# 16bit-v0_5.net
KiCad netlist of a schematic drawn in EAGLE
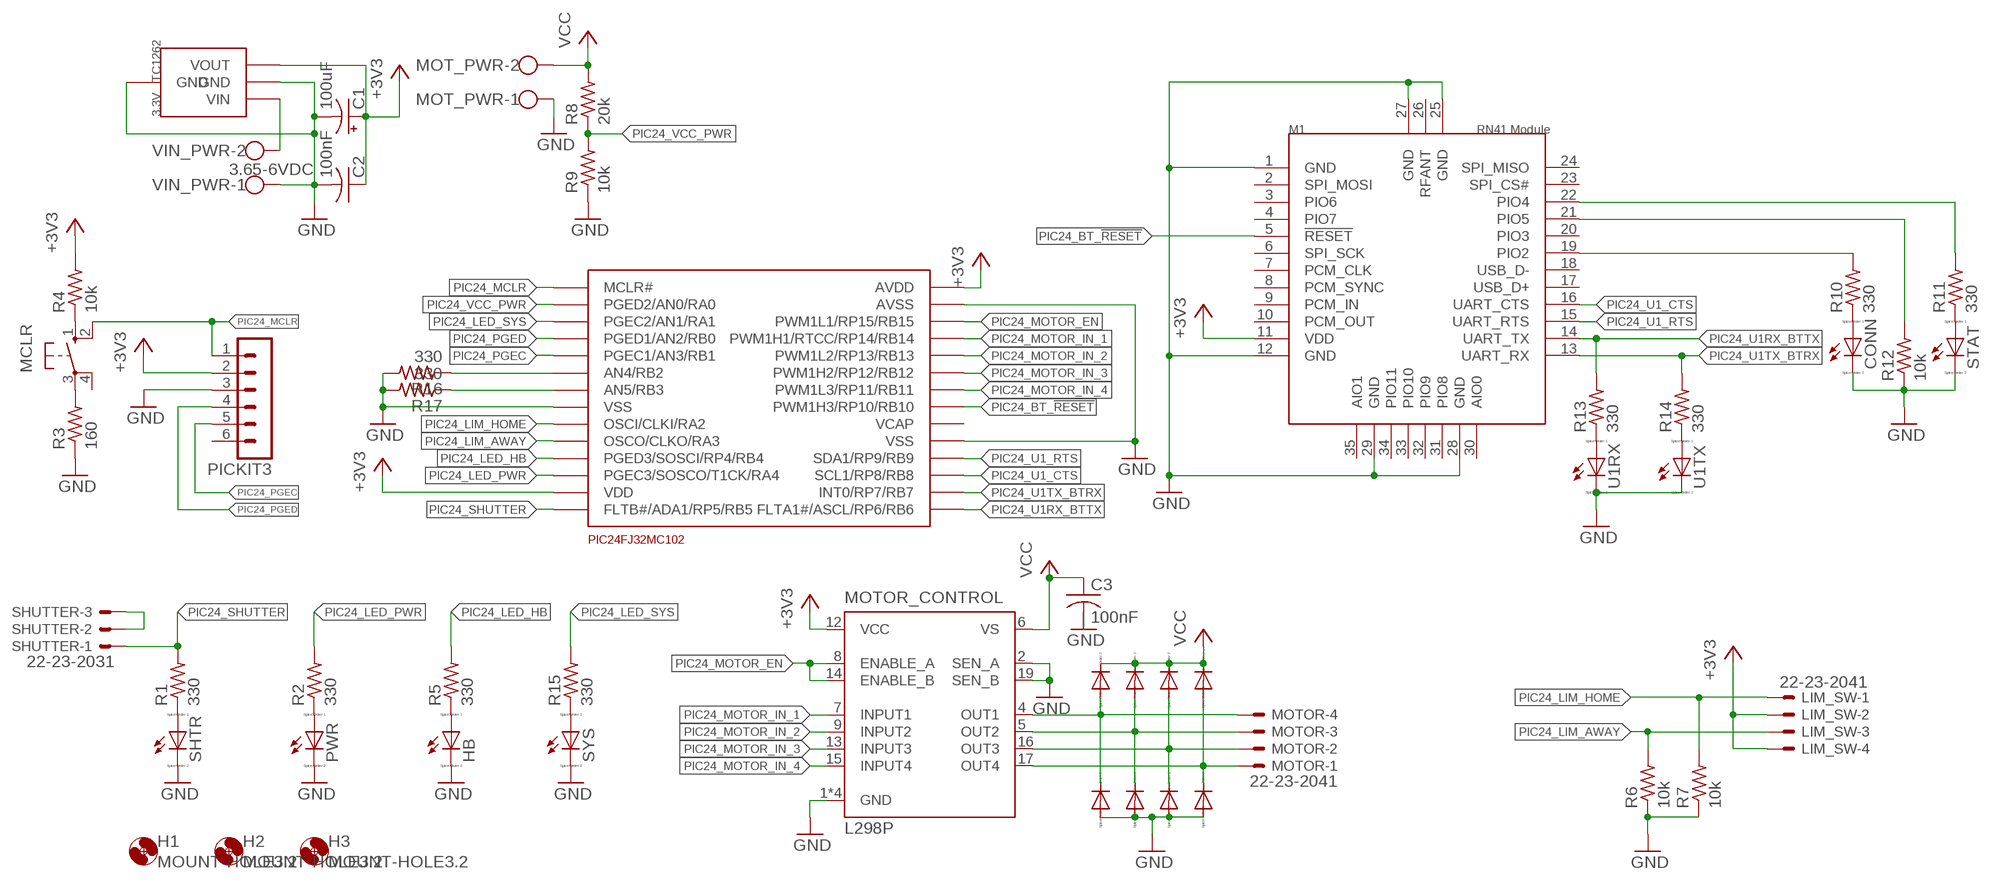
[diagram p0: schematic, sheet 1]

(export (version "E")
  (design (tool "Eeschema 10.0.6"))
  (components
    (comp (ref "C1")
      (value "100uF")
      (footprint "eagle-import:E2,5-7")
      (libsource (lib "eagle-import") (part "CPOL-USE2.5-7"))
    )
    (comp (ref "C2")
      (value "100nF")
      (footprint "eagle-import:C0402")
      (libsource (lib "eagle-import") (part "C-USC0402"))
    )
    (comp (ref "C3")
      (value "100nF")
      (footprint "eagle-import:C0402")
      (libsource (lib "eagle-import") (part "C-USC0402"))
    )
    (comp (ref "CONN")
      (value "LED_ESML0603")
      (footprint "eagle-import:LED_SML0603")
      (libsource (lib "eagle-import") (part "LED_ESML0603"))
    )
    (comp (ref "D1")
      (value "DIODE-SMB")
      (footprint "eagle-import:SMB")
      (libsource (lib "eagle-import") (part "DIODE-SMB"))
    )
    (comp (ref "D2")
      (value "DIODE-SMB")
      (footprint "eagle-import:SMB")
      (libsource (lib "eagle-import") (part "DIODE-SMB"))
    )
    (comp (ref "D3")
      (value "DIODE-SMB")
      (footprint "eagle-import:SMB")
      (libsource (lib "eagle-import") (part "DIODE-SMB"))
    )
    (comp (ref "D4")
      (value "DIODE-SMB")
      (footprint "eagle-import:SMB")
      (libsource (lib "eagle-import") (part "DIODE-SMB"))
    )
    (comp (ref "D5")
      (value "DIODE-SMB")
      (footprint "eagle-import:SMB")
      (libsource (lib "eagle-import") (part "DIODE-SMB"))
    )
    (comp (ref "D6")
      (value "DIODE-SMB")
      (footprint "eagle-import:SMB")
      (libsource (lib "eagle-import") (part "DIODE-SMB"))
    )
    (comp (ref "D7")
      (value "DIODE-SMB")
      (footprint "eagle-import:SMB")
      (libsource (lib "eagle-import") (part "DIODE-SMB"))
    )
    (comp (ref "D8")
      (value "DIODE-SMB")
      (footprint "eagle-import:SMB")
      (libsource (lib "eagle-import") (part "DIODE-SMB"))
    )
    (comp (ref "H1")
      (value "MOUNT-HOLE3.2")
      (footprint "eagle-import:3,2")
      (libsource (lib "eagle-import") (part "MOUNT-HOLE3.2"))
    )
    (comp (ref "H2")
      (value "MOUNT-HOLE3.2")
      (footprint "eagle-import:3,2")
      (libsource (lib "eagle-import") (part "MOUNT-HOLE3.2"))
    )
    (comp (ref "H3")
      (value "MOUNT-HOLE3.2")
      (footprint "eagle-import:3,2")
      (libsource (lib "eagle-import") (part "MOUNT-HOLE3.2"))
    )
    (comp (ref "HB")
      (value "LED_ESML0603")
      (footprint "eagle-import:LED_SML0603")
      (libsource (lib "eagle-import") (part "LED_ESML0603"))
    )
    (comp (ref "LIM_SW")
      (value "22-23-2041")
      (footprint "eagle-import:22-23-2041")
      (fields (field (name "MF") "MOLEX"))
      (libsource (lib "eagle-import") (part "22-23-2041"))
    )
    (comp (ref "MCLR")
      (value "10-XX")
      (footprint "eagle-import:B3F-10XX")
      (fields (field (name "MPN") "B3F-1000"))
      (libsource (lib "eagle-import") (part "10-XX"))
    )
    (comp (ref "MOTOR")
      (value "22-23-2041")
      (footprint "eagle-import:22-23-2041")
      (fields (field (name "MF") "MOLEX"))
      (libsource (lib "eagle-import") (part "22-23-2041"))
    )
    (comp (ref "MOTOR_CONTROL")
      (value "L298P")
      (footprint "eagle-import:POWERSO-20")
      (libsource (lib "eagle-import") (part "L298P"))
    )
    (comp (ref "MOT_PWR")
      (value "W237-102")
      (footprint "eagle-import:W237-102")
      (fields (field (name "MPN") "237-102"))
      (libsource (lib "eagle-import") (part "W237-102"))
    )
    (comp (ref "PICKIT3")
      (value "MA06-1")
      (footprint "eagle-import:MA06-1")
      (libsource (lib "eagle-import") (part "MA06-1"))
    )
    (comp (ref "PWR")
      (value "LED_ESML0603")
      (footprint "eagle-import:LED_SML0603")
      (libsource (lib "eagle-import") (part "LED_ESML0603"))
    )
    (comp (ref "R1")
      (value "330")
      (footprint "eagle-import:R0603")
      (libsource (lib "eagle-import") (part "R-US_R0603"))
    )
    (comp (ref "R2")
      (value "330")
      (footprint "eagle-import:R0603")
      (libsource (lib "eagle-import") (part "R-US_R0603"))
    )
    (comp (ref "R3")
      (value "160")
      (footprint "eagle-import:R0603")
      (libsource (lib "eagle-import") (part "R-US_R0603"))
    )
    (comp (ref "R4")
      (value "10k")
      (footprint "eagle-import:R0603")
      (libsource (lib "eagle-import") (part "R-US_R0603"))
    )
    (comp (ref "R5")
      (value "330")
      (footprint "eagle-import:R0603")
      (libsource (lib "eagle-import") (part "R-US_R0603"))
    )
    (comp (ref "R6")
      (value "10k")
      (footprint "eagle-import:R0603")
      (libsource (lib "eagle-import") (part "R-US_R0603"))
    )
    (comp (ref "R7")
      (value "10k")
      (footprint "eagle-import:R0603")
      (libsource (lib "eagle-import") (part "R-US_R0603"))
    )
    (comp (ref "R8")
      (value "20k")
      (footprint "eagle-import:R0603")
      (libsource (lib "eagle-import") (part "R-US_R0603"))
    )
    (comp (ref "R9")
      (value "10k")
      (footprint "eagle-import:R0603")
      (libsource (lib "eagle-import") (part "R-US_R0603"))
    )
    (comp (ref "R10")
      (value "330")
      (footprint "eagle-import:R0603")
      (libsource (lib "eagle-import") (part "R-US_R0603"))
    )
    (comp (ref "R11")
      (value "330")
      (footprint "eagle-import:R0603")
      (libsource (lib "eagle-import") (part "R-US_R0603"))
    )
    (comp (ref "R12")
      (value "10k")
      (footprint "eagle-import:R0603")
      (libsource (lib "eagle-import") (part "R-US_R0603"))
    )
    (comp (ref "R13")
      (value "330")
      (footprint "eagle-import:R0603")
      (libsource (lib "eagle-import") (part "R-US_R0603"))
    )
    (comp (ref "R14")
      (value "330")
      (footprint "eagle-import:R0603")
      (libsource (lib "eagle-import") (part "R-US_R0603"))
    )
    (comp (ref "R15")
      (value "330")
      (footprint "eagle-import:R0603")
      (libsource (lib "eagle-import") (part "R-US_R0603"))
    )
    (comp (ref "R16")
      (value "330")
      (footprint "eagle-import:R0603")
      (libsource (lib "eagle-import") (part "R-US_R0603"))
    )
    (comp (ref "R17")
      (value "330")
      (footprint "eagle-import:R0603")
      (libsource (lib "eagle-import") (part "R-US_R0603"))
    )
    (comp (ref "SHTR")
      (value "LED_ESML0603")
      (footprint "eagle-import:LED_SML0603")
      (libsource (lib "eagle-import") (part "LED_ESML0603"))
    )
    (comp (ref "SHUTTER")
      (value "22-23-2031")
      (footprint "eagle-import:22-23-2031")
      (fields (field (name "MF") "MOLEX"))
      (libsource (lib "eagle-import") (part "22-23-2031"))
    )
    (comp (ref "STAT")
      (value "LED_ESML0603")
      (footprint "eagle-import:LED_SML0603")
      (libsource (lib "eagle-import") (part "LED_ESML0603"))
    )
    (comp (ref "SYS")
      (value "LED_ESML0603")
      (footprint "eagle-import:LED_SML0603")
      (libsource (lib "eagle-import") (part "LED_ESML0603"))
    )
    (comp (ref "U$1")
      (value "PIC24FJ32MC102")
      (footprint "eagle-import:PIC2428-SOIC")
      (libsource (lib "eagle-import") (part "PIC24FJ32MC102"))
    )
    (comp (ref "U$2")
      (value "RN41N")
      (footprint "eagle-import:RN41N")
      (libsource (lib "eagle-import") (part "RN41N"))
    )
    (comp (ref "U$3")
      (value "TC1262-3.3VDBTR")
      (footprint "eagle-import:TO-261-4")
      (libsource (lib "eagle-import") (part "TC1262-3.3VDBTR"))
    )
    (comp (ref "U1RX")
      (value "LED_ESML0603")
      (footprint "eagle-import:LED_SML0603")
      (libsource (lib "eagle-import") (part "LED_ESML0603"))
    )
    (comp (ref "U1TX")
      (value "LED_ESML0603")
      (footprint "eagle-import:LED_SML0603")
      (libsource (lib "eagle-import") (part "LED_ESML0603"))
    )
    (comp (ref "VIN_PWR")
      (value "3.65-6VDC")
      (footprint "eagle-import:W237-102")
      (fields (field (name "MPN") "237-102"))
      (libsource (lib "eagle-import") (part "W237-102"))
    )
  )
  (nets
    (net (code "1") (name "+3V3") (class "Default")
      (node (ref "C1") (pin "+") (pinfunction "+_+") (pintype "passive"))
      (node (ref "C2") (pin "1") (pinfunction "1_1") (pintype "passive"))
      (node (ref "LIM_SW") (pin "2") (pinfunction "S_2") (pintype "passive"))
      (node (ref "LIM_SW") (pin "4") (pinfunction "S_4") (pintype "passive"))
      (node (ref "MOTOR_CONTROL") (pin "12") (pinfunction "VCC_12") (pintype "power_in"))
      (node (ref "PICKIT3") (pin "2") (pinfunction "2_2") (pintype "passive"))
      (node (ref "R4") (pin "2") (pinfunction "2_2") (pintype "passive"))
      (node (ref "U$1") (pin "AVDD") (pinfunction "AVDD_AVDD") (pintype "bidirectional"))
      (node (ref "U$1") (pin "VDD") (pinfunction "VDD_VDD") (pintype "bidirectional"))
      (node (ref "U$2") (pin "11") (pinfunction "VDD_11") (pintype "bidirectional"))
      (node (ref "U$3") (pin "P$3") (pinfunction "VOUT_P$3") (pintype "bidirectional"))
    )
    (net (code "2") (name "/PIC24_BT_~{RESET}") (class "Default")
      (node (ref "U$1") (pin "RB10") (pinfunction "PWM1H3/RP10/RB10_RB10") (pintype "bidirectional"))
      (node (ref "U$2") (pin "5") (pinfunction "~{RESET}_5") (pintype "bidirectional"))
    )
    (net (code "3") (name "GND") (class "Default")
      (node (ref "C1") (pin "-") (pinfunction "-_-") (pintype "passive"))
      (node (ref "C2") (pin "2") (pinfunction "2_2") (pintype "passive"))
      (node (ref "C3") (pin "2") (pinfunction "2_2") (pintype "passive"))
      (node (ref "CONN") (pin "C") (pinfunction "C_C") (pintype "passive"))
      (node (ref "D5") (pin "A") (pinfunction "A_A") (pintype "passive"))
      (node (ref "D6") (pin "A") (pinfunction "A_A") (pintype "passive"))
      (node (ref "D7") (pin "A") (pinfunction "A_A") (pintype "passive"))
      (node (ref "D8") (pin "A") (pinfunction "A_A") (pintype "passive"))
      (node (ref "HB") (pin "C") (pinfunction "C_C") (pintype "passive"))
      (node (ref "MOTOR_CONTROL") (pin "1") (pinfunction "GND_1") (pintype "power_in"))
      (node (ref "MOTOR_CONTROL") (pin "10") (pinfunction "GND_10") (pintype "power_in"))
      (node (ref "MOTOR_CONTROL") (pin "11") (pinfunction "GND_11") (pintype "power_in"))
      (node (ref "MOTOR_CONTROL") (pin "19") (pinfunction "SEN_B_19") (pintype "input"))
      (node (ref "MOTOR_CONTROL") (pin "2") (pinfunction "SEN_A_2") (pintype "input"))
      (node (ref "MOTOR_CONTROL") (pin "20") (pinfunction "GND_20") (pintype "power_in"))
      (node (ref "MOT_PWR") (pin "1") (pinfunction "KL_1") (pintype "passive"))
      (node (ref "PICKIT3") (pin "3") (pinfunction "3_3") (pintype "passive"))
      (node (ref "PWR") (pin "C") (pinfunction "C_C") (pintype "passive"))
      (node (ref "R12") (pin "1") (pinfunction "1_1") (pintype "passive"))
      (node (ref "R16") (pin "2") (pinfunction "2_2") (pintype "passive"))
      (node (ref "R17") (pin "2") (pinfunction "2_2") (pintype "passive"))
      (node (ref "R3") (pin "1") (pinfunction "1_1") (pintype "passive"))
      (node (ref "R6") (pin "1") (pinfunction "1_1") (pintype "passive"))
      (node (ref "R7") (pin "1") (pinfunction "1_1") (pintype "passive"))
      (node (ref "R9") (pin "1") (pinfunction "1_1") (pintype "passive"))
      (node (ref "SHTR") (pin "C") (pinfunction "C_C") (pintype "passive"))
      (node (ref "STAT") (pin "C") (pinfunction "C_C") (pintype "passive"))
      (node (ref "SYS") (pin "C") (pinfunction "C_C") (pintype "passive"))
      (node (ref "U$1") (pin "AVSS") (pinfunction "AVSS_AVSS") (pintype "bidirectional"))
      (node (ref "U$1") (pin "VSS@19") (pinfunction "VSS_VSS@19") (pintype "bidirectional"))
      (node (ref "U$1") (pin "VSS@8") (pinfunction "VSS_VSS@8") (pintype "bidirectional"))
      (node (ref "U$2") (pin "1") (pinfunction "GND_1") (pintype "bidirectional"))
      (node (ref "U$2") (pin "12") (pinfunction "GND_12") (pintype "bidirectional"))
      (node (ref "U$2") (pin "25") (pinfunction "GND_25") (pintype "bidirectional"))
      (node (ref "U$2") (pin "27") (pinfunction "GND_27") (pintype "bidirectional"))
      (node (ref "U$2") (pin "28") (pinfunction "GND_28") (pintype "bidirectional"))
      (node (ref "U$2") (pin "29") (pinfunction "GND_29") (pintype "bidirectional"))
      (node (ref "U$3") (pin "P$2") (pinfunction "GND_P$2") (pintype "bidirectional"))
      (node (ref "U$3") (pin "P$4") (pinfunction "GND_P$4") (pintype "bidirectional"))
      (node (ref "U1RX") (pin "C") (pinfunction "C_C") (pintype "passive"))
      (node (ref "U1TX") (pin "C") (pinfunction "C_C") (pintype "passive"))
      (node (ref "VIN_PWR") (pin "1") (pinfunction "KL_1") (pintype "passive"))
    )
    (net (code "4") (name "Net-(CONN-PadA)") (class "Default")
      (node (ref "CONN") (pin "A") (pinfunction "A_A") (pintype "passive"))
      (node (ref "R10") (pin "1") (pinfunction "1_1") (pintype "passive"))
    )
    (net (code "5") (name "Net-(HB-PadA)") (class "Default")
      (node (ref "HB") (pin "A") (pinfunction "A_A") (pintype "passive"))
      (node (ref "R5") (pin "1") (pinfunction "1_1") (pintype "passive"))
    )
    (net (code "6") (name "Net-(MCLR-P)") (class "Default")
      (node (ref "MCLR") (pin "3") (pinfunction "P_3") (pintype "passive"))
      (node (ref "R3") (pin "2") (pinfunction "2_2") (pintype "passive"))
    )
    (net (code "7") (name "Net-(MCLR-S)") (class "Default")
      (node (ref "MCLR") (pin "1") (pinfunction "S_1") (pintype "passive"))
      (node (ref "R4") (pin "1") (pinfunction "1_1") (pintype "passive"))
    )
    (net (code "8") (name "Net-(MOTORA-S)") (class "Default")
      (node (ref "D4") (pin "A") (pinfunction "A_A") (pintype "passive"))
      (node (ref "D8") (pin "C") (pinfunction "C_C") (pintype "passive"))
      (node (ref "MOTOR") (pin "1") (pinfunction "S_1") (pintype "passive"))
      (node (ref "MOTOR_CONTROL") (pin "17") (pinfunction "OUT4_17") (pintype "output"))
    )
    (net (code "9") (name "Net-(MOTORB-S)") (class "Default")
      (node (ref "D3") (pin "A") (pinfunction "A_A") (pintype "passive"))
      (node (ref "D7") (pin "C") (pinfunction "C_C") (pintype "passive"))
      (node (ref "MOTOR") (pin "2") (pinfunction "S_2") (pintype "passive"))
      (node (ref "MOTOR_CONTROL") (pin "16") (pinfunction "OUT3_16") (pintype "output"))
    )
    (net (code "10") (name "Net-(MOTORC-S)") (class "Default")
      (node (ref "D2") (pin "A") (pinfunction "A_A") (pintype "passive"))
      (node (ref "D6") (pin "C") (pinfunction "C_C") (pintype "passive"))
      (node (ref "MOTOR") (pin "3") (pinfunction "S_3") (pintype "passive"))
      (node (ref "MOTOR_CONTROL") (pin "5") (pinfunction "OUT2_5") (pintype "output"))
    )
    (net (code "11") (name "Net-(MOTORD-S)") (class "Default")
      (node (ref "D1") (pin "A") (pinfunction "A_A") (pintype "passive"))
      (node (ref "D5") (pin "C") (pinfunction "C_C") (pintype "passive"))
      (node (ref "MOTOR") (pin "4") (pinfunction "S_4") (pintype "passive"))
      (node (ref "MOTOR_CONTROL") (pin "4") (pinfunction "OUT1_4") (pintype "output"))
    )
    (net (code "12") (name "Net-(PWR-PadA)") (class "Default")
      (node (ref "PWR") (pin "A") (pinfunction "A_A") (pintype "passive"))
      (node (ref "R2") (pin "1") (pinfunction "1_1") (pintype "passive"))
    )
    (net (code "13") (name "Net-(R1-Pad1)") (class "Default")
      (node (ref "R1") (pin "1") (pinfunction "1_1") (pintype "passive"))
      (node (ref "SHTR") (pin "A") (pinfunction "A_A") (pintype "passive"))
    )
    (net (code "14") (name "Net-(R11-Pad1)") (class "Default")
      (node (ref "R11") (pin "1") (pinfunction "1_1") (pintype "passive"))
      (node (ref "STAT") (pin "A") (pinfunction "A_A") (pintype "passive"))
    )
    (net (code "15") (name "Net-(R13-Pad1)") (class "Default")
      (node (ref "R13") (pin "1") (pinfunction "1_1") (pintype "passive"))
      (node (ref "U1RX") (pin "A") (pinfunction "A_A") (pintype "passive"))
    )
    (net (code "16") (name "Net-(R14-Pad1)") (class "Default")
      (node (ref "R14") (pin "1") (pinfunction "1_1") (pintype "passive"))
      (node (ref "U1TX") (pin "A") (pinfunction "A_A") (pintype "passive"))
    )
    (net (code "17") (name "Net-(R15-Pad1)") (class "Default")
      (node (ref "R15") (pin "1") (pinfunction "1_1") (pintype "passive"))
      (node (ref "SYS") (pin "A") (pinfunction "A_A") (pintype "passive"))
    )
    (net (code "18") (name "Net-(SHUTTERB-S)") (class "Default")
      (node (ref "SHUTTER") (pin "2") (pinfunction "S_2") (pintype "passive"))
      (node (ref "SHUTTER") (pin "3") (pinfunction "S_3") (pintype "passive"))
    )
    (net (code "19") (name "Net-(U$1-AN4{slash}RB2)") (class "Default")
      (node (ref "R16") (pin "1") (pinfunction "1_1") (pintype "passive"))
      (node (ref "U$1") (pin "RB2") (pinfunction "AN4/RB2_RB2") (pintype "bidirectional"))
    )
    (net (code "20") (name "Net-(U$1-AN5{slash}RB3)") (class "Default")
      (node (ref "R17") (pin "1") (pinfunction "1_1") (pintype "passive"))
      (node (ref "U$1") (pin "RB3") (pinfunction "AN5/RB3_RB3") (pintype "bidirectional"))
    )
    (net (code "21") (name "Net-(U$2-PIO2)") (class "Default")
      (node (ref "R10") (pin "2") (pinfunction "2_2") (pintype "passive"))
      (node (ref "U$2") (pin "19") (pinfunction "PIO2_19") (pintype "bidirectional"))
    )
    (net (code "22") (name "Net-(U$2-PIO4)") (class "Default")
      (node (ref "R11") (pin "2") (pinfunction "2_2") (pintype "passive"))
      (node (ref "U$2") (pin "22") (pinfunction "PIO4_22") (pintype "bidirectional"))
    )
    (net (code "23") (name "Net-(U$2-PIO5)") (class "Default")
      (node (ref "R12") (pin "2") (pinfunction "2_2") (pintype "passive"))
      (node (ref "U$2") (pin "21") (pinfunction "PIO5_21") (pintype "bidirectional"))
    )
    (net (code "24") (name "Net-(U$3-VIN)") (class "Default")
      (node (ref "U$3") (pin "P$1") (pinfunction "VIN_P$1") (pintype "bidirectional"))
      (node (ref "VIN_PWR") (pin "2") (pinfunction "KL_2") (pintype "passive"))
    )
    (net (code "25") (name "PIC24_LED_HB") (class "Default")
      (node (ref "R5") (pin "2") (pinfunction "2_2") (pintype "passive"))
      (node (ref "U$1") (pin "RB4") (pinfunction "PGED3/SOSCI/RP4/RB4_RB4") (pintype "bidirectional"))
    )
    (net (code "26") (name "PIC24_LED_PWR") (class "Default")
      (node (ref "R2") (pin "2") (pinfunction "2_2") (pintype "passive"))
      (node (ref "U$1") (pin "RA4") (pinfunction "PGEC3/SOSCO/T1CK/RA4_RA4") (pintype "bidirectional"))
    )
    (net (code "27") (name "PIC24_LED_SYS") (class "Default")
      (node (ref "R15") (pin "2") (pinfunction "2_2") (pintype "passive"))
      (node (ref "U$1") (pin "RA1") (pinfunction "PGEC2/AN1/RA1_RA1") (pintype "bidirectional"))
    )
    (net (code "28") (name "PIC24_LIM_AWAY") (class "Default")
      (node (ref "LIM_SW") (pin "3") (pinfunction "S_3") (pintype "passive"))
      (node (ref "R6") (pin "2") (pinfunction "2_2") (pintype "passive"))
      (node (ref "U$1") (pin "RA3") (pinfunction "OSCO/CLKO/RA3_RA3") (pintype "bidirectional"))
    )
    (net (code "29") (name "PIC24_LIM_HOME") (class "Default")
      (node (ref "LIM_SW") (pin "1") (pinfunction "S_1") (pintype "passive"))
      (node (ref "R7") (pin "2") (pinfunction "2_2") (pintype "passive"))
      (node (ref "U$1") (pin "RA2") (pinfunction "OSCI/CLKI/RA2_RA2") (pintype "bidirectional"))
    )
    (net (code "30") (name "PIC24_MCLR") (class "Default")
      (node (ref "MCLR") (pin "2") (pinfunction "S1_2") (pintype "passive"))
      (node (ref "PICKIT3") (pin "1") (pinfunction "1_1") (pintype "passive"))
      (node (ref "U$1") (pin "MCLR#") (pinfunction "MCLR#_MCLR#") (pintype "bidirectional"))
    )
    (net (code "31") (name "PIC24_MOTOR_EN") (class "Default")
      (node (ref "MOTOR_CONTROL") (pin "14") (pinfunction "ENABLE_B_14") (pintype "input"))
      (node (ref "MOTOR_CONTROL") (pin "8") (pinfunction "ENABLE_A_8") (pintype "input"))
      (node (ref "U$1") (pin "RB15") (pinfunction "PWM1L1/RP15/RB15_RB15") (pintype "bidirectional"))
    )
    (net (code "32") (name "PIC24_MOTOR_IN_1") (class "Default")
      (node (ref "MOTOR_CONTROL") (pin "7") (pinfunction "INPUT1_7") (pintype "input"))
      (node (ref "U$1") (pin "RB14") (pinfunction "PWM1H1/RTCC/RP14/RB14_RB14") (pintype "bidirectional"))
    )
    (net (code "33") (name "PIC24_MOTOR_IN_2") (class "Default")
      (node (ref "MOTOR_CONTROL") (pin "9") (pinfunction "INPUT2_9") (pintype "input"))
      (node (ref "U$1") (pin "RB13") (pinfunction "PWM1L2/RP13/RB13_RB13") (pintype "bidirectional"))
    )
    (net (code "34") (name "PIC24_MOTOR_IN_3") (class "Default")
      (node (ref "MOTOR_CONTROL") (pin "13") (pinfunction "INPUT3_13") (pintype "input"))
      (node (ref "U$1") (pin "RB12") (pinfunction "PWM1H2/RP12/RB12_RB12") (pintype "bidirectional"))
    )
    (net (code "35") (name "PIC24_MOTOR_IN_4") (class "Default")
      (node (ref "MOTOR_CONTROL") (pin "15") (pinfunction "INPUT4_15") (pintype "input"))
      (node (ref "U$1") (pin "RB11") (pinfunction "PWM1L3/RP11/RB11_RB11") (pintype "bidirectional"))
    )
    (net (code "36") (name "PIC24_PGEC") (class "Default")
      (node (ref "PICKIT3") (pin "5") (pinfunction "5_5") (pintype "passive"))
      (node (ref "U$1") (pin "PGEC1") (pinfunction "PGEC1/AN3/RB1_PGEC1") (pintype "bidirectional"))
    )
    (net (code "37") (name "PIC24_PGED") (class "Default")
      (node (ref "PICKIT3") (pin "4") (pinfunction "4_4") (pintype "passive"))
      (node (ref "U$1") (pin "PGED1") (pinfunction "PGED1/AN2/RB0_PGED1") (pintype "bidirectional"))
    )
    (net (code "38") (name "PIC24_SHUTTER") (class "Default")
      (node (ref "R1") (pin "2") (pinfunction "2_2") (pintype "passive"))
      (node (ref "SHUTTER") (pin "1") (pinfunction "S_1") (pintype "passive"))
      (node (ref "U$1") (pin "RB5") (pinfunction "FLTB#/ADA1/RP5/RB5_RB5") (pintype "bidirectional"))
    )
    (net (code "39") (name "PIC24_U1RX_BTTX") (class "Default")
      (node (ref "R13") (pin "2") (pinfunction "2_2") (pintype "passive"))
      (node (ref "U$1") (pin "RB6") (pinfunction "FLTA1#/ASCL/RP6/RB6_RB6") (pintype "bidirectional"))
      (node (ref "U$2") (pin "14") (pinfunction "UART_TX_14") (pintype "bidirectional"))
    )
    (net (code "40") (name "PIC24_U1TX_BTRX") (class "Default")
      (node (ref "R14") (pin "2") (pinfunction "2_2") (pintype "passive"))
      (node (ref "U$1") (pin "RB7") (pinfunction "INT0/RP7/RB7_RB7") (pintype "bidirectional"))
      (node (ref "U$2") (pin "13") (pinfunction "UART_RX_13") (pintype "bidirectional"))
    )
    (net (code "41") (name "PIC24_U1_CTS") (class "Default")
      (node (ref "U$1") (pin "RB8") (pinfunction "SCL1/RP8/RB8_RB8") (pintype "bidirectional"))
      (node (ref "U$2") (pin "16") (pinfunction "UART_CTS_16") (pintype "bidirectional"))
    )
    (net (code "42") (name "PIC24_U1_RTS") (class "Default")
      (node (ref "U$1") (pin "RB9") (pinfunction "SDA1/RP9/RB9_RB9") (pintype "bidirectional"))
      (node (ref "U$2") (pin "15") (pinfunction "UART_RTS_15") (pintype "bidirectional"))
    )
    (net (code "43") (name "PIC24_VCC_PWR") (class "Default")
      (node (ref "R8") (pin "1") (pinfunction "1_1") (pintype "passive"))
      (node (ref "R9") (pin "2") (pinfunction "2_2") (pintype "passive"))
      (node (ref "U$1") (pin "RA0") (pinfunction "PGED2/AN0/RA0_RA0") (pintype "bidirectional"))
    )
    (net (code "44") (name "VCC") (class "Default")
      (node (ref "C3") (pin "1") (pinfunction "1_1") (pintype "passive"))
      (node (ref "D1") (pin "C") (pinfunction "C_C") (pintype "passive"))
      (node (ref "D2") (pin "C") (pinfunction "C_C") (pintype "passive"))
      (node (ref "D3") (pin "C") (pinfunction "C_C") (pintype "passive"))
      (node (ref "D4") (pin "C") (pinfunction "C_C") (pintype "passive"))
      (node (ref "MOTOR_CONTROL") (pin "6") (pinfunction "VS_6") (pintype "power_in"))
      (node (ref "MOT_PWR") (pin "2") (pinfunction "KL_2") (pintype "passive"))
      (node (ref "R8") (pin "2") (pinfunction "2_2") (pintype "passive"))
    )
    (net (code "45") (name "unconnected-(MCLR-P1-Pad4)") (class "Default")
      (node (ref "MCLR") (pin "4") (pinfunction "P1_4") (pintype "passive"))
    )
    (net (code "46") (name "unconnected-(PICKIT3-Pad6)") (class "Default")
      (node (ref "PICKIT3") (pin "6") (pinfunction "6_6") (pintype "passive"))
    )
    (net (code "47") (name "unconnected-(U$1-PadVCAP)") (class "Default")
      (node (ref "U$1") (pin "VCAP") (pinfunction "VCAP_VCAP") (pintype "bidirectional"))
    )
    (net (code "48") (name "unconnected-(U$2-AIO0-Pad30)") (class "Default")
      (node (ref "U$2") (pin "30") (pinfunction "AIO0_30") (pintype "bidirectional"))
    )
    (net (code "49") (name "unconnected-(U$2-AIO1-Pad35)") (class "Default")
      (node (ref "U$2") (pin "35") (pinfunction "AIO1_35") (pintype "bidirectional"))
    )
    (net (code "50") (name "unconnected-(U$2-PCM_CLK-Pad7)") (class "Default")
      (node (ref "U$2") (pin "7") (pinfunction "PCM_CLK_7") (pintype "bidirectional"))
    )
    (net (code "51") (name "unconnected-(U$2-PCM_IN-Pad9)") (class "Default")
      (node (ref "U$2") (pin "9") (pinfunction "PCM_IN_9") (pintype "bidirectional"))
    )
    (net (code "52") (name "unconnected-(U$2-PCM_OUT-Pad10)") (class "Default")
      (node (ref "U$2") (pin "10") (pinfunction "PCM_OUT_10") (pintype "bidirectional"))
    )
    (net (code "53") (name "unconnected-(U$2-PCM_SYNC-Pad8)") (class "Default")
      (node (ref "U$2") (pin "8") (pinfunction "PCM_SYNC_8") (pintype "bidirectional"))
    )
    (net (code "54") (name "unconnected-(U$2-PIO3-Pad20)") (class "Default")
      (node (ref "U$2") (pin "20") (pinfunction "PIO3_20") (pintype "bidirectional"))
    )
    (net (code "55") (name "unconnected-(U$2-PIO6-Pad3)") (class "Default")
      (node (ref "U$2") (pin "3") (pinfunction "PIO6_3") (pintype "bidirectional"))
    )
    (net (code "56") (name "unconnected-(U$2-PIO7-Pad4)") (class "Default")
      (node (ref "U$2") (pin "4") (pinfunction "PIO7_4") (pintype "bidirectional"))
    )
    (net (code "57") (name "unconnected-(U$2-PIO8-Pad31)") (class "Default")
      (node (ref "U$2") (pin "31") (pinfunction "PIO8_31") (pintype "bidirectional"))
    )
    (net (code "58") (name "unconnected-(U$2-PIO9-Pad32)") (class "Default")
      (node (ref "U$2") (pin "32") (pinfunction "PIO9_32") (pintype "bidirectional"))
    )
    (net (code "59") (name "unconnected-(U$2-PIO10-Pad33)") (class "Default")
      (node (ref "U$2") (pin "33") (pinfunction "PIO10_33") (pintype "bidirectional"))
    )
    (net (code "60") (name "unconnected-(U$2-PIO11-Pad34)") (class "Default")
      (node (ref "U$2") (pin "34") (pinfunction "PIO11_34") (pintype "bidirectional"))
    )
    (net (code "61") (name "unconnected-(U$2-RFANT-Pad26)") (class "Default")
      (node (ref "U$2") (pin "26") (pinfunction "RFANT_26") (pintype "bidirectional"))
    )
    (net (code "62") (name "unconnected-(U$2-SPI_CS#-Pad23)") (class "Default")
      (node (ref "U$2") (pin "23") (pinfunction "SPI_CS#_23") (pintype "bidirectional"))
    )
    (net (code "63") (name "unconnected-(U$2-SPI_MISO-Pad24)") (class "Default")
      (node (ref "U$2") (pin "24") (pinfunction "SPI_MISO_24") (pintype "bidirectional"))
    )
    (net (code "64") (name "unconnected-(U$2-SPI_MOSI-Pad2)") (class "Default")
      (node (ref "U$2") (pin "2") (pinfunction "SPI_MOSI_2") (pintype "bidirectional"))
    )
    (net (code "65") (name "unconnected-(U$2-SPI_SCK-Pad6)") (class "Default")
      (node (ref "U$2") (pin "6") (pinfunction "SPI_SCK_6") (pintype "bidirectional"))
    )
    (net (code "66") (name "unconnected-(U$2-USB_D+-Pad17)") (class "Default")
      (node (ref "U$2") (pin "17") (pinfunction "USB_D+_17") (pintype "bidirectional"))
    )
    (net (code "67") (name "unconnected-(U$2-USB_D--Pad18)") (class "Default")
      (node (ref "U$2") (pin "18") (pinfunction "USB_D-_18") (pintype "bidirectional"))
    )
  )
)
